# VIC20_Diag_UP.net
KiCad netlist of a schematic drawn in EAGLE
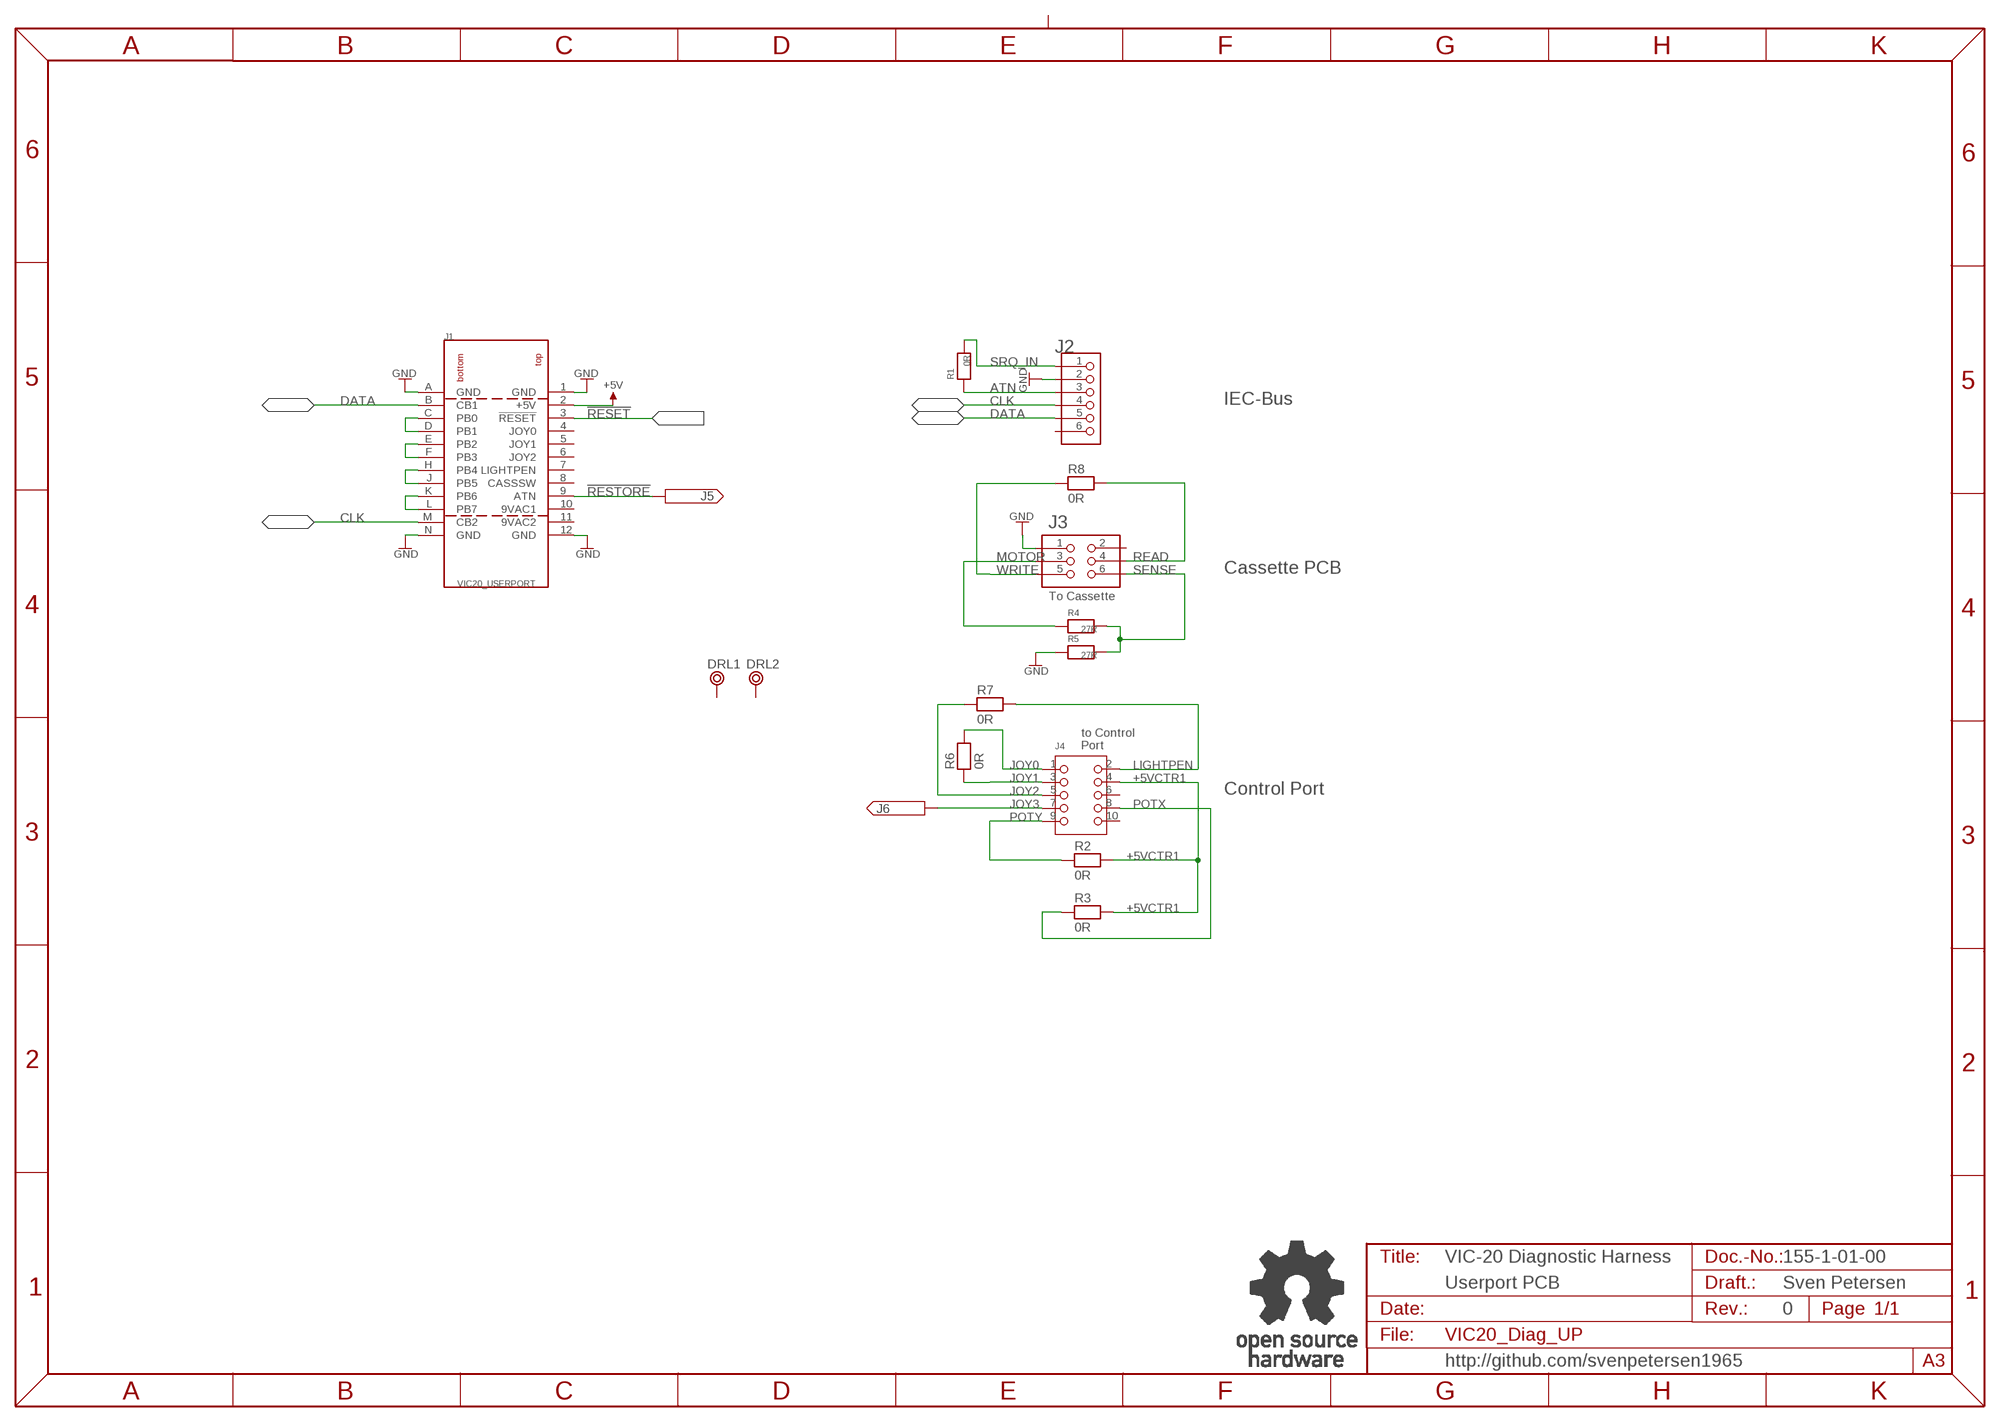
[diagram p0: schematic, sheet 1]

(export (version "E")
  (design (tool "Eeschema 10.0.6"))
  (components
    (comp (ref "DRL1")
      (value "BOHR3,5")
      (footprint "eagle-import:BOHR3,5")
      (libsource (lib "eagle-import") (part "BOHR3,5"))
    )
    (comp (ref "DRL2")
      (value "BOHR3,5")
      (footprint "eagle-import:BOHR3,5")
      (libsource (lib "eagle-import") (part "BOHR3,5"))
    )
    (comp (ref "J1")
      (value "VIC20_USERPORT")
      (footprint "eagle-import:USERPORT")
      (libsource (lib "eagle-import") (part "VIC20_USERPORT"))
    )
    (comp (ref "J2")
      (value "6410-6P")
      (footprint "eagle-import:6410-6P")
      (libsource (lib "eagle-import") (part "6410-6P"))
    )
    (comp (ref "J3")
      (value "2X03WV")
      (footprint "eagle-import:2X03WV")
      (libsource (lib "eagle-import") (part "2X03WV"))
    )
    (comp (ref "J4")
      (value "2X05WV")
      (footprint "eagle-import:2X05WV")
      (libsource (lib "eagle-import") (part "2X05WV"))
    )
    (comp (ref "J5")
      (value "PINHD-1X1")
      (footprint "eagle-import:1X01")
      (libsource (lib "eagle-import") (part "PINHD-1X1"))
    )
    (comp (ref "J6")
      (value "PINHD-1X1")
      (footprint "eagle-import:1X01")
      (libsource (lib "eagle-import") (part "PINHD-1X1"))
    )
    (comp (ref "R1")
      (value "0R")
      (footprint "eagle-import:R-10")
      (libsource (lib "eagle-import") (part "RES04"))
    )
    (comp (ref "R2")
      (value "0R")
      (footprint "eagle-import:R-10")
      (libsource (lib "eagle-import") (part "RES04"))
    )
    (comp (ref "R3")
      (value "0R")
      (footprint "eagle-import:R-10")
      (libsource (lib "eagle-import") (part "RES04"))
    )
    (comp (ref "R4")
      (value "27R")
      (footprint "eagle-import:R-10")
      (libsource (lib "eagle-import") (part "RES04"))
    )
    (comp (ref "R5")
      (value "27R")
      (footprint "eagle-import:R-10")
      (libsource (lib "eagle-import") (part "RES04"))
    )
    (comp (ref "R6")
      (value "0R")
      (footprint "eagle-import:R-10")
      (libsource (lib "eagle-import") (part "RES04"))
    )
    (comp (ref "R7")
      (value "0R")
      (footprint "eagle-import:R-10")
      (libsource (lib "eagle-import") (part "RES04"))
    )
    (comp (ref "R8")
      (value "0R")
      (footprint "eagle-import:R-10")
      (libsource (lib "eagle-import") (part "RES04"))
    )
    (comp (ref "U$2")
      (value "OPEN_SOURCE_HW")
      (footprint "eagle-import:OPENHW")
      (libsource (lib "eagle-import") (part "OPEN_SOURCE_HW"))
    )
  )
  (nets
    (net (code "1") (name "+5V") (class "Default")
      (node (ref "J1") (pin "2") (pinfunction "+5V_2") (pintype "power_in"))
    )
    (net (code "2") (name "/+5VCTR1") (class "Default")
      (node (ref "J4") (pin "4") (pinfunction "4_4") (pintype "passive"))
      (node (ref "R2") (pin "2") (pinfunction "2_2") (pintype "passive"))
      (node (ref "R3") (pin "2") (pinfunction "2_2") (pintype "passive"))
    )
    (net (code "3") (name "/9VAC1") (class "Default")
      (node (ref "J1") (pin "10") (pinfunction "9VAC1_10") (pintype "power_in"))
    )
    (net (code "4") (name "/9VAC2") (class "Default")
      (node (ref "J1") (pin "11") (pinfunction "9VAC2_11") (pintype "power_in"))
    )
    (net (code "5") (name "/ATN") (class "Default")
      (node (ref "J2") (pin "3") (pinfunction "3_3") (pintype "passive"))
      (node (ref "R1") (pin "1") (pinfunction "1_1") (pintype "passive"))
    )
    (net (code "6") (name "/CLK") (class "Default")
      (node (ref "J1") (pin "M") (pinfunction "CB2_M") (pintype "bidirectional"))
      (node (ref "J2") (pin "4") (pinfunction "4_4") (pintype "passive"))
    )
    (net (code "7") (name "/DATA") (class "Default")
      (node (ref "J1") (pin "B") (pinfunction "CB1_B") (pintype "input"))
      (node (ref "J2") (pin "5") (pinfunction "5_5") (pintype "passive"))
    )
    (net (code "8") (name "/JOY0") (class "Default")
      (node (ref "J4") (pin "1") (pinfunction "1_1") (pintype "passive"))
      (node (ref "R6") (pin "2") (pinfunction "2_2") (pintype "passive"))
    )
    (net (code "9") (name "/JOY1") (class "Default")
      (node (ref "J4") (pin "3") (pinfunction "3_3") (pintype "passive"))
      (node (ref "R6") (pin "1") (pinfunction "1_1") (pintype "passive"))
    )
    (net (code "10") (name "/JOY2") (class "Default")
      (node (ref "J4") (pin "5") (pinfunction "5_5") (pintype "passive"))
      (node (ref "R7") (pin "1") (pinfunction "1_1") (pintype "passive"))
    )
    (net (code "11") (name "/JOY3") (class "Default")
      (node (ref "J4") (pin "7") (pinfunction "7_7") (pintype "passive"))
      (node (ref "J6") (pin "1") (pinfunction "1_1") (pintype "passive"))
    )
    (net (code "12") (name "/LIGHTPEN") (class "Default")
      (node (ref "J4") (pin "2") (pinfunction "2_2") (pintype "passive"))
      (node (ref "R7") (pin "2") (pinfunction "2_2") (pintype "passive"))
    )
    (net (code "13") (name "/MOTOR") (class "Default")
      (node (ref "J3") (pin "3") (pinfunction "3_3") (pintype "passive"))
      (node (ref "R4") (pin "1") (pinfunction "1_1") (pintype "passive"))
    )
    (net (code "14") (name "/POTX") (class "Default")
      (node (ref "J4") (pin "8") (pinfunction "8_8") (pintype "passive"))
      (node (ref "R3") (pin "1") (pinfunction "1_1") (pintype "passive"))
    )
    (net (code "15") (name "/POTY") (class "Default")
      (node (ref "J4") (pin "9") (pinfunction "9_9") (pintype "passive"))
      (node (ref "R2") (pin "1") (pinfunction "1_1") (pintype "passive"))
    )
    (net (code "16") (name "/READ") (class "Default")
      (node (ref "J3") (pin "4") (pinfunction "4_4") (pintype "passive"))
      (node (ref "R8") (pin "2") (pinfunction "2_2") (pintype "passive"))
    )
    (net (code "17") (name "/SENSE") (class "Default")
      (node (ref "J3") (pin "6") (pinfunction "6_6") (pintype "passive"))
      (node (ref "R4") (pin "2") (pinfunction "2_2") (pintype "passive"))
      (node (ref "R5") (pin "2") (pinfunction "2_2") (pintype "passive"))
    )
    (net (code "18") (name "/SRQ_IN") (class "Default")
      (node (ref "J2") (pin "1") (pinfunction "1_1") (pintype "passive"))
      (node (ref "R1") (pin "2") (pinfunction "2_2") (pintype "passive"))
    )
    (net (code "19") (name "/WRITE") (class "Default")
      (node (ref "J3") (pin "5") (pinfunction "5_5") (pintype "passive"))
      (node (ref "R8") (pin "1") (pinfunction "1_1") (pintype "passive"))
    )
    (net (code "20") (name "/~{RESET}") (class "Default")
      (node (ref "J1") (pin "3") (pinfunction "~{RESET}_3") (pintype "bidirectional"))
    )
    (net (code "21") (name "/~{RESTORE}") (class "Default")
      (node (ref "J1") (pin "9") (pinfunction "ATN_9") (pintype "bidirectional"))
      (node (ref "J5") (pin "1") (pinfunction "1_1") (pintype "passive"))
    )
    (net (code "22") (name "GND") (class "Default")
      (node (ref "J1") (pin "1") (pinfunction "GND_1") (pintype "power_in"))
      (node (ref "J1") (pin "12") (pinfunction "GND_12") (pintype "power_in"))
      (node (ref "J1") (pin "A") (pinfunction "GND_A") (pintype "power_in"))
      (node (ref "J1") (pin "N") (pinfunction "GND_N") (pintype "power_in"))
      (node (ref "J2") (pin "2") (pinfunction "2_2") (pintype "passive"))
      (node (ref "J3") (pin "1") (pinfunction "1_1") (pintype "passive"))
      (node (ref "R5") (pin "1") (pinfunction "1_1") (pintype "passive"))
    )
    (net (code "23") (name "Net-(J1-PB0)") (class "Default")
      (node (ref "J1") (pin "C") (pinfunction "PB0_C") (pintype "bidirectional"))
      (node (ref "J1") (pin "D") (pinfunction "PB1_D") (pintype "bidirectional"))
    )
    (net (code "24") (name "Net-(J1-PB2)") (class "Default")
      (node (ref "J1") (pin "E") (pinfunction "PB2_E") (pintype "bidirectional"))
      (node (ref "J1") (pin "F") (pinfunction "PB3_F") (pintype "bidirectional"))
    )
    (net (code "25") (name "Net-(J1-PB4)") (class "Default")
      (node (ref "J1") (pin "H") (pinfunction "PB4_H") (pintype "bidirectional"))
      (node (ref "J1") (pin "J") (pinfunction "PB5_J") (pintype "bidirectional"))
    )
    (net (code "26") (name "Net-(J1-PB6)") (class "Default")
      (node (ref "J1") (pin "K") (pinfunction "PB6_K") (pintype "bidirectional"))
      (node (ref "J1") (pin "L") (pinfunction "PB7_L") (pintype "bidirectional"))
    )
    (net (code "27") (name "unconnected-(DRL1-PadP$1)") (class "Default")
      (node (ref "DRL1") (pin "P$1") (pinfunction "P$1_P$1") (pintype "passive"))
    )
    (net (code "28") (name "unconnected-(DRL2-PadP$1)") (class "Default")
      (node (ref "DRL2") (pin "P$1") (pinfunction "P$1_P$1") (pintype "passive"))
    )
    (net (code "29") (name "unconnected-(J1-CASSSW-Pad8)") (class "Default")
      (node (ref "J1") (pin "8") (pinfunction "CASSSW_8") (pintype "bidirectional"))
    )
    (net (code "30") (name "unconnected-(J1-JOY0-Pad4)") (class "Default")
      (node (ref "J1") (pin "4") (pinfunction "JOY0_4") (pintype "input"))
    )
    (net (code "31") (name "unconnected-(J1-JOY1-Pad5)") (class "Default")
      (node (ref "J1") (pin "5") (pinfunction "JOY1_5") (pintype "bidirectional"))
    )
    (net (code "32") (name "unconnected-(J1-JOY2-Pad6)") (class "Default")
      (node (ref "J1") (pin "6") (pinfunction "JOY2_6") (pintype "input"))
    )
    (net (code "33") (name "unconnected-(J1-LIGHTPEN-Pad7)") (class "Default")
      (node (ref "J1") (pin "7") (pinfunction "LIGHTPEN_7") (pintype "bidirectional"))
    )
    (net (code "34") (name "unconnected-(J2-Pad6)") (class "Default")
      (node (ref "J2") (pin "6") (pinfunction "6_6") (pintype "passive"))
    )
    (net (code "35") (name "unconnected-(J3-Pad2)") (class "Default")
      (node (ref "J3") (pin "2") (pinfunction "2_2") (pintype "passive"))
    )
    (net (code "36") (name "unconnected-(J4-Pad6)") (class "Default")
      (node (ref "J4") (pin "6") (pinfunction "6_6") (pintype "passive"))
    )
    (net (code "37") (name "unconnected-(J4-Pad10)") (class "Default")
      (node (ref "J4") (pin "10") (pinfunction "10_10") (pintype "passive"))
    )
  )
)
